# usb.net
KiCad netlist of a schematic drawn in EAGLE
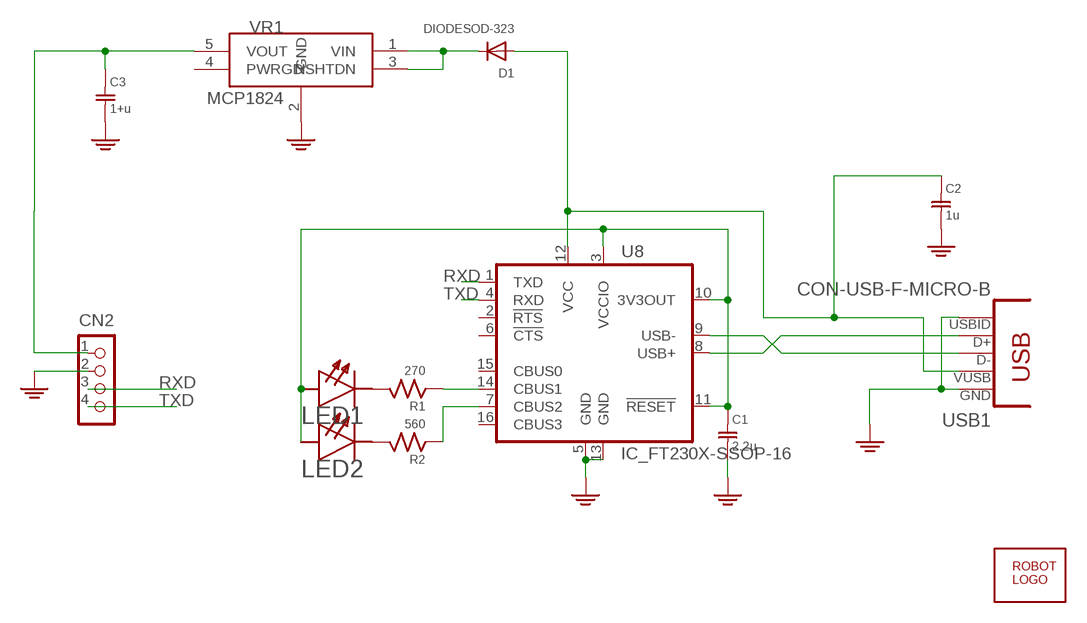
[diagram p0: schematic, sheet 1]

(export (version "E")
  (design (tool "Eeschema 10.0.6"))
  (components
    (comp (ref "C1")
      (value "2.2u")
      (footprint "eagle-import:SMD0603")
      (libsource (lib "eagle-import") (part "C0603"))
    )
    (comp (ref "C2")
      (value "1u")
      (footprint "eagle-import:SMD0603")
      (libsource (lib "eagle-import") (part "C0603"))
    )
    (comp (ref "C3")
      (value "1+u")
      (footprint "eagle-import:SMD0603")
      (libsource (lib "eagle-import") (part "C0603"))
    )
    (comp (ref "CN2")
      (value "CON_HEADER_1X04")
      (footprint "eagle-import:M1X4")
      (libsource (lib "eagle-import") (part "CON_HEADER_1X04"))
    )
    (comp (ref "D1")
      (value "DIODESOD-323")
      (footprint "eagle-import:SOD-323")
      (libsource (lib "eagle-import") (part "DIODESOD-323"))
    )
    (comp (ref "LED1")
      (value "GREEN")
      (footprint "eagle-import:SMD0603D")
      (libsource (lib "eagle-import") (part "LED"))
    )
    (comp (ref "LED2")
      (value "ORANGE")
      (footprint "eagle-import:SMD0603D")
      (libsource (lib "eagle-import") (part "LED"))
    )
    (comp (ref "R1")
      (value "270")
      (footprint "eagle-import:SMD0603")
      (libsource (lib "eagle-import") (part "R0603"))
    )
    (comp (ref "R2")
      (value "560")
      (footprint "eagle-import:SMD0603")
      (libsource (lib "eagle-import") (part "R0603"))
    )
    (comp (ref "U$1")
      (value "ROBOTMAN-LOGO2")
      (footprint "eagle-import:ROBOTMAN-LOGO2")
      (libsource (lib "eagle-import") (part "ROBOTMAN-LOGO2"))
    )
    (comp (ref "U8")
      (value "IC_FT230X-SSOP-16")
      (footprint "eagle-import:SSOP-16-FTDI")
      (libsource (lib "eagle-import") (part "IC_FT230X-SSOP-16"))
    )
    (comp (ref "USB1")
      (value "CON-USB-F-MICRO-B")
      (footprint "eagle-import:CONN_USB_MICRO-B")
      (libsource (lib "eagle-import") (part "CON-USB-F-MICRO-B"))
    )
    (comp (ref "VR1")
      (value "MCP1824")
      (footprint "eagle-import:SOT-23-5")
      (libsource (lib "eagle-import") (part "MCP1824"))
    )
  )
  (nets
    (net (code "1") (name "/RXD") (class "Default")
      (node (ref "CN2") (pin "3") (pinfunction "3_3") (pintype "bidirectional"))
      (node (ref "U8") (pin "1") (pinfunction "TXD_1") (pintype "output"))
    )
    (net (code "2") (name "/TXD") (class "Default")
      (node (ref "CN2") (pin "4") (pinfunction "4_4") (pintype "bidirectional"))
      (node (ref "U8") (pin "4") (pinfunction "RXD_4") (pintype "input"))
    )
    (net (code "3") (name "Net-(C1-P$1)") (class "Default")
      (node (ref "C1") (pin "1") (pinfunction "P$1_1") (pintype "passive"))
      (node (ref "LED1") (pin "A") (pinfunction "A_A") (pintype "passive"))
      (node (ref "LED2") (pin "A") (pinfunction "A_A") (pintype "passive"))
      (node (ref "U8") (pin "10") (pinfunction "3V3OUT_10") (pintype "power_in"))
      (node (ref "U8") (pin "11") (pinfunction "~{RESET}_11") (pintype "bidirectional"))
      (node (ref "U8") (pin "3") (pinfunction "VCCIO_3") (pintype "power_in"))
    )
    (net (code "4") (name "Net-(C2-P$1)") (class "Default")
      (node (ref "C2") (pin "1") (pinfunction "P$1_1") (pintype "passive"))
      (node (ref "D1") (pin "A") (pinfunction "A_A") (pintype "passive"))
      (node (ref "U8") (pin "12") (pinfunction "VCC_12") (pintype "power_in"))
      (node (ref "USB1") (pin "P1") (pinfunction "VUSB_P1") (pintype "bidirectional"))
    )
    (net (code "5") (name "Net-(C3-P$1)") (class "Default")
      (node (ref "C3") (pin "1") (pinfunction "P$1_1") (pintype "passive"))
      (node (ref "CN2") (pin "1") (pinfunction "1_1") (pintype "bidirectional"))
      (node (ref "VR1") (pin "5") (pinfunction "VOUT_5") (pintype "bidirectional"))
    )
    (net (code "6") (name "Net-(R1-P$1)") (class "Default")
      (node (ref "R1") (pin "1") (pinfunction "P$1_1") (pintype "passive"))
      (node (ref "U8") (pin "14") (pinfunction "CBUS1_14") (pintype "bidirectional"))
    )
    (net (code "7") (name "Net-(R1-P$2)") (class "Default")
      (node (ref "LED1") (pin "C") (pinfunction "C_C") (pintype "passive"))
      (node (ref "R1") (pin "2") (pinfunction "P$2_2") (pintype "passive"))
    )
    (net (code "8") (name "Net-(R2-P$1)") (class "Default")
      (node (ref "R2") (pin "1") (pinfunction "P$1_1") (pintype "passive"))
      (node (ref "U8") (pin "7") (pinfunction "CBUS2_7") (pintype "bidirectional"))
    )
    (net (code "9") (name "Net-(R2-P$2)") (class "Default")
      (node (ref "LED2") (pin "C") (pinfunction "C_C") (pintype "passive"))
      (node (ref "R2") (pin "2") (pinfunction "P$2_2") (pintype "passive"))
    )
    (net (code "10") (name "Net-(U8-USB+)") (class "Default")
      (node (ref "U8") (pin "8") (pinfunction "USB+_8") (pintype "output"))
      (node (ref "USB1") (pin "P3") (pinfunction "D+_P3") (pintype "bidirectional"))
    )
    (net (code "11") (name "Net-(U8-USB-)") (class "Default")
      (node (ref "U8") (pin "9") (pinfunction "USB-_9") (pintype "input"))
      (node (ref "USB1") (pin "P2") (pinfunction "D-_P2") (pintype "bidirectional"))
    )
    (net (code "12") (name "Net-(VR1-NSHTDN)") (class "Default")
      (node (ref "D1") (pin "C") (pinfunction "C_C") (pintype "passive"))
      (node (ref "VR1") (pin "1") (pinfunction "VIN_1") (pintype "bidirectional"))
      (node (ref "VR1") (pin "3") (pinfunction "NSHTDN_3") (pintype "bidirectional"))
    )
    (net (code "13") (name "PWR-GND") (class "Default")
      (node (ref "C1") (pin "2") (pinfunction "P$2_2") (pintype "passive"))
      (node (ref "C2") (pin "2") (pinfunction "P$2_2") (pintype "passive"))
      (node (ref "C3") (pin "2") (pinfunction "P$2_2") (pintype "passive"))
      (node (ref "CN2") (pin "2") (pinfunction "2_2") (pintype "bidirectional"))
      (node (ref "U8") (pin "13") (pinfunction "GND_13") (pintype "power_in"))
      (node (ref "U8") (pin "5") (pinfunction "GND_5") (pintype "power_in"))
      (node (ref "USB1") (pin "P4") (pinfunction "USBID_P4") (pintype "bidirectional"))
      (node (ref "USB1") (pin "P5") (pinfunction "GND_P5") (pintype "bidirectional"))
      (node (ref "VR1") (pin "2") (pinfunction "GND_2") (pintype "bidirectional"))
    )
    (net (code "14") (name "unconnected-(U8-CBUS0-Pad15)") (class "Default")
      (node (ref "U8") (pin "15") (pinfunction "CBUS0_15") (pintype "bidirectional"))
    )
    (net (code "15") (name "unconnected-(U8-CBUS3-Pad16)") (class "Default")
      (node (ref "U8") (pin "16") (pinfunction "CBUS3_16") (pintype "bidirectional"))
    )
    (net (code "16") (name "unconnected-(U8-~{CTS}-Pad6)") (class "Default")
      (node (ref "U8") (pin "6") (pinfunction "~{CTS}_6") (pintype "bidirectional"))
    )
    (net (code "17") (name "unconnected-(U8-~{RTS}-Pad2)") (class "Default")
      (node (ref "U8") (pin "2") (pinfunction "~{RTS}_2") (pintype "bidirectional"))
    )
    (net (code "18") (name "unconnected-(VR1-PWRGD-Pad4)") (class "Default")
      (node (ref "VR1") (pin "4") (pinfunction "PWRGD_4") (pintype "bidirectional"))
    )
  )
)
